# HMP.net
KiCad netlist of a schematic drawn in EasyEDA Pro
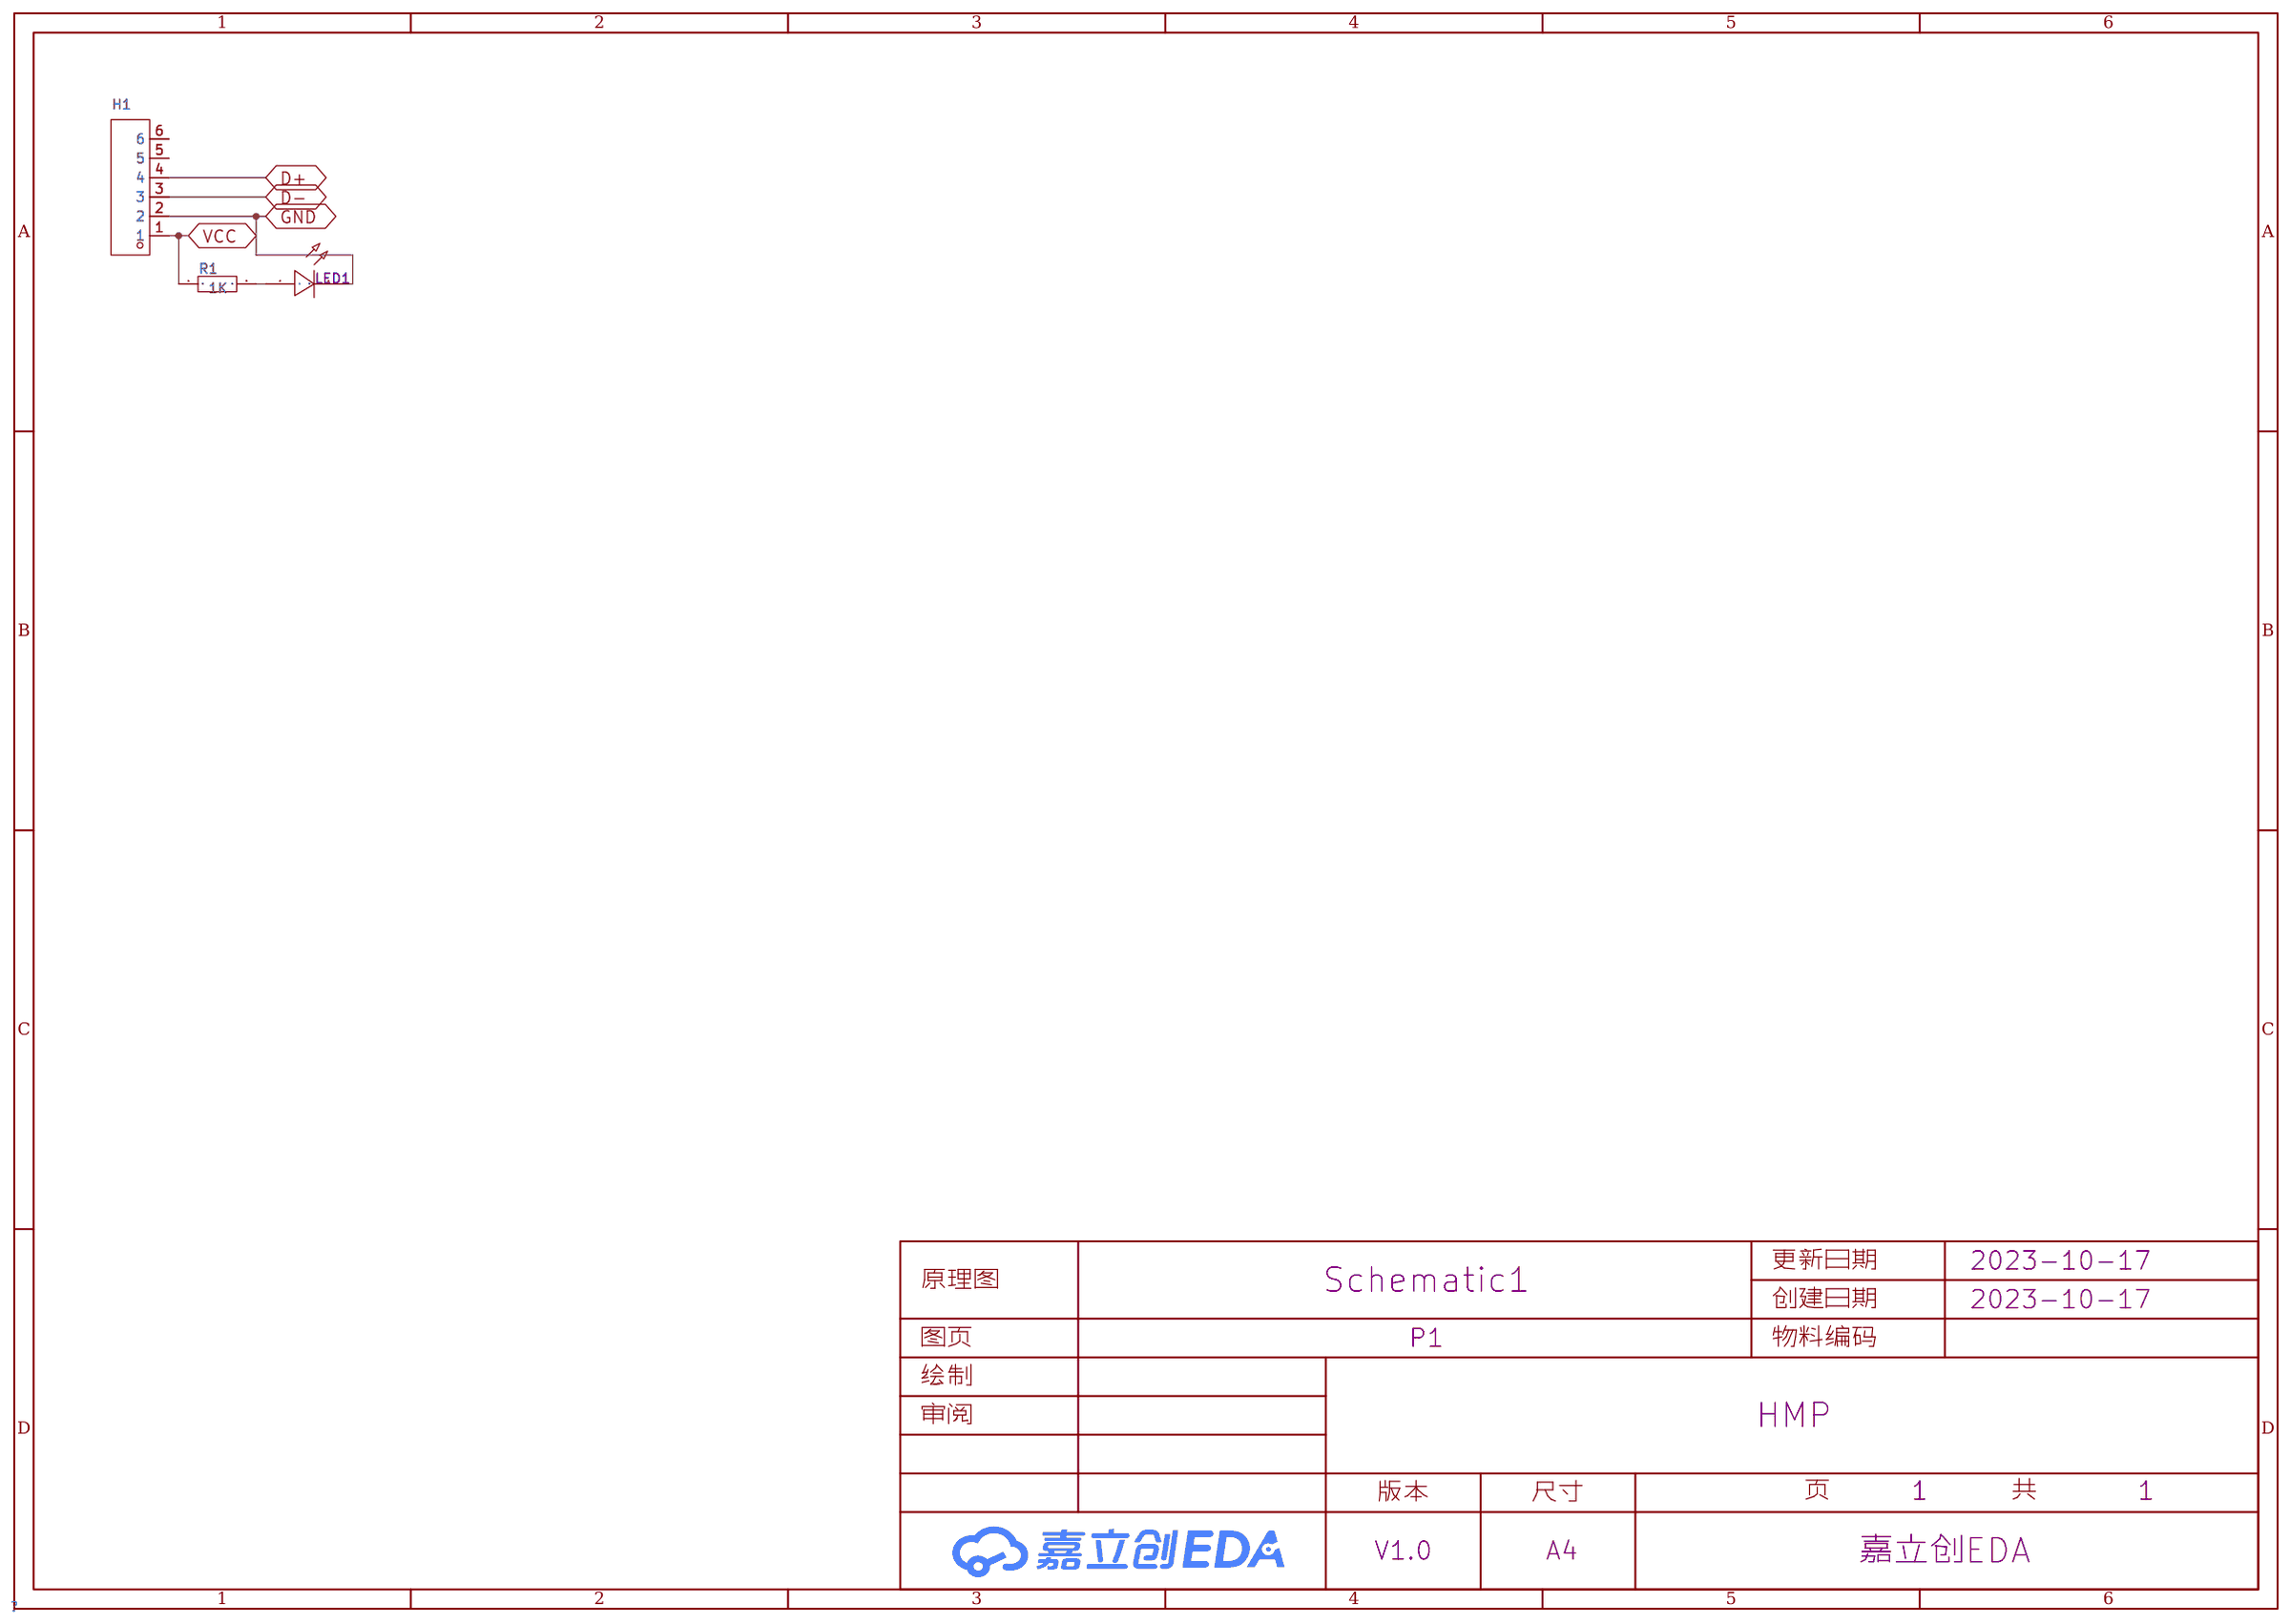
[diagram p0: schematic sheet]

(export (version "E")
  (design (tool "Eeschema 10.0.6"))
  (components
    (comp (ref "H1")
      (value "~")
      (footprint "easyedapro:HDR-TH_6P-P2.54-V-F")
      (libsource (lib "easyedapro") (part "Header-Female-2.54_1x6"))
    )
    (comp (ref "LED1")
      (value "~")
      (footprint "easyedapro:LED_0402")
      (libsource (lib "easyedapro") (part "LED_G"))
    )
    (comp (ref "R1") (value "1K") (footprint "easyedapro:R0402") (libsource (lib "easyedapro") (part "电阻")))
  )
  (nets
    (net (code "1") (name "D+") (class "Default")
      (node (ref "H1") (pin "4") (pinfunction "4_4") (pintype "unspecified"))
    )
    (net (code "2") (name "D-") (class "Default")
      (node (ref "H1") (pin "3") (pinfunction "3_3") (pintype "unspecified"))
    )
    (net (code "3") (name "GND") (class "Default")
      (node (ref "H1") (pin "2") (pinfunction "2_2") (pintype "unspecified"))
      (node (ref "LED1") (pin "1") (pinfunction "C_1") (pintype "input"))
    )
    (net (code "4") (name "Net-(LED1-A)") (class "Default")
      (node (ref "LED1") (pin "2") (pinfunction "A_2") (pintype "input"))
      (node (ref "R1") (pin "2") (pinfunction "2_2") (pintype "input"))
    )
    (net (code "5") (name "VCC") (class "Default")
      (node (ref "H1") (pin "1") (pinfunction "1_1") (pintype "unspecified"))
      (node (ref "R1") (pin "1") (pinfunction "1_1") (pintype "input"))
    )
    (net (code "6") (name "unconnected-(H1-Pad5)") (class "Default")
      (node (ref "H1") (pin "5") (pinfunction "5_5") (pintype "unspecified"))
    )
    (net (code "7") (name "unconnected-(H1-Pad6)") (class "Default")
      (node (ref "H1") (pin "6") (pinfunction "6_6") (pintype "unspecified"))
    )
  )
)
